# joystickV1.net
KiCad netlist of a schematic drawn in EAGLE
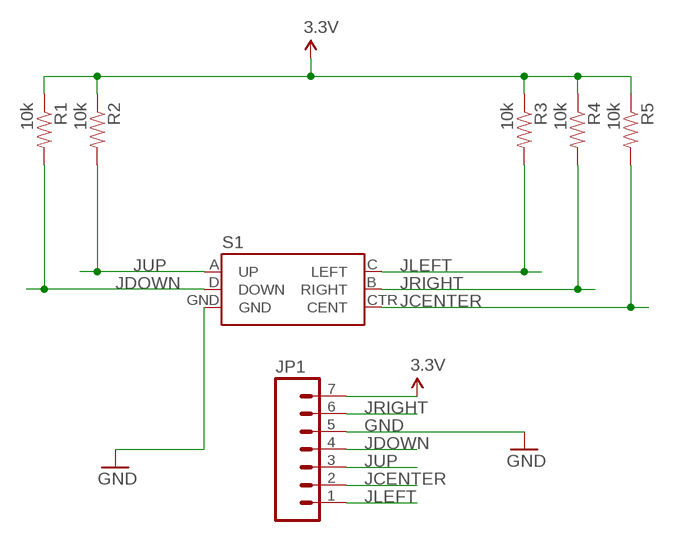
[diagram p0: schematic, sheet 1]

(export (version "E")
  (design (tool "Eeschema 10.0.6"))
  (components
    (comp (ref "JP1")
      (value "M07")
      (footprint "eagle-import:1X07")
      (libsource (lib "eagle-import") (part "M07"))
    )
    (comp (ref "R1")
      (value "10k")
      (footprint "eagle-import:0603-RES")
      (libsource (lib "eagle-import") (part "RESISTOR0603-RES"))
    )
    (comp (ref "R2")
      (value "10k")
      (footprint "eagle-import:0603-RES")
      (libsource (lib "eagle-import") (part "RESISTOR0603-RES"))
    )
    (comp (ref "R3")
      (value "10k")
      (footprint "eagle-import:0603-RES")
      (libsource (lib "eagle-import") (part "RESISTOR0603-RES"))
    )
    (comp (ref "R4")
      (value "10k")
      (footprint "eagle-import:0603-RES")
      (libsource (lib "eagle-import") (part "RESISTOR0603-RES"))
    )
    (comp (ref "R5")
      (value "10k")
      (footprint "eagle-import:0603-RES")
      (libsource (lib "eagle-import") (part "RESISTOR0603-RES"))
    )
    (comp (ref "S1")
      (value "JOYSTICK_MINI")
      (footprint "eagle-import:JOYSTICK_MINI")
      (libsource (lib "eagle-import") (part "JOYSTICK_MINI"))
    )
  )
  (nets
    (net (code "1") (name "/JCENTER") (class "Default")
      (node (ref "JP1") (pin "2") (pinfunction "2_2") (pintype "passive"))
      (node (ref "R5") (pin "2") (pinfunction "2_2") (pintype "passive"))
      (node (ref "S1") (pin "CTR") (pinfunction "CENT_CTR") (pintype "bidirectional"))
    )
    (net (code "2") (name "/JDOWN") (class "Default")
      (node (ref "JP1") (pin "4") (pinfunction "4_4") (pintype "passive"))
      (node (ref "R1") (pin "2") (pinfunction "2_2") (pintype "passive"))
      (node (ref "S1") (pin "D") (pinfunction "DOWN_D") (pintype "bidirectional"))
    )
    (net (code "3") (name "/JLEFT") (class "Default")
      (node (ref "JP1") (pin "1") (pinfunction "1_1") (pintype "passive"))
      (node (ref "R3") (pin "2") (pinfunction "2_2") (pintype "passive"))
      (node (ref "S1") (pin "C") (pinfunction "LEFT_C") (pintype "bidirectional"))
    )
    (net (code "4") (name "/JRIGHT") (class "Default")
      (node (ref "JP1") (pin "6") (pinfunction "6_6") (pintype "passive"))
      (node (ref "R4") (pin "2") (pinfunction "2_2") (pintype "passive"))
      (node (ref "S1") (pin "B") (pinfunction "RIGHT_B") (pintype "bidirectional"))
    )
    (net (code "5") (name "/JUP") (class "Default")
      (node (ref "JP1") (pin "3") (pinfunction "3_3") (pintype "passive"))
      (node (ref "R2") (pin "2") (pinfunction "2_2") (pintype "passive"))
      (node (ref "S1") (pin "A") (pinfunction "UP_A") (pintype "bidirectional"))
    )
    (net (code "6") (name "3.3V") (class "Default")
      (node (ref "JP1") (pin "7") (pinfunction "7_7") (pintype "passive"))
      (node (ref "R1") (pin "1") (pinfunction "1_1") (pintype "passive"))
      (node (ref "R2") (pin "1") (pinfunction "1_1") (pintype "passive"))
      (node (ref "R3") (pin "1") (pinfunction "1_1") (pintype "passive"))
      (node (ref "R4") (pin "1") (pinfunction "1_1") (pintype "passive"))
      (node (ref "R5") (pin "1") (pinfunction "1_1") (pintype "passive"))
    )
    (net (code "7") (name "GND") (class "Default")
      (node (ref "JP1") (pin "5") (pinfunction "5_5") (pintype "passive"))
      (node (ref "S1") (pin "GND") (pinfunction "GND_GND") (pintype "bidirectional"))
    )
  )
)
